# untitled.net
KiCad netlist of a schematic drawn in EAGLE
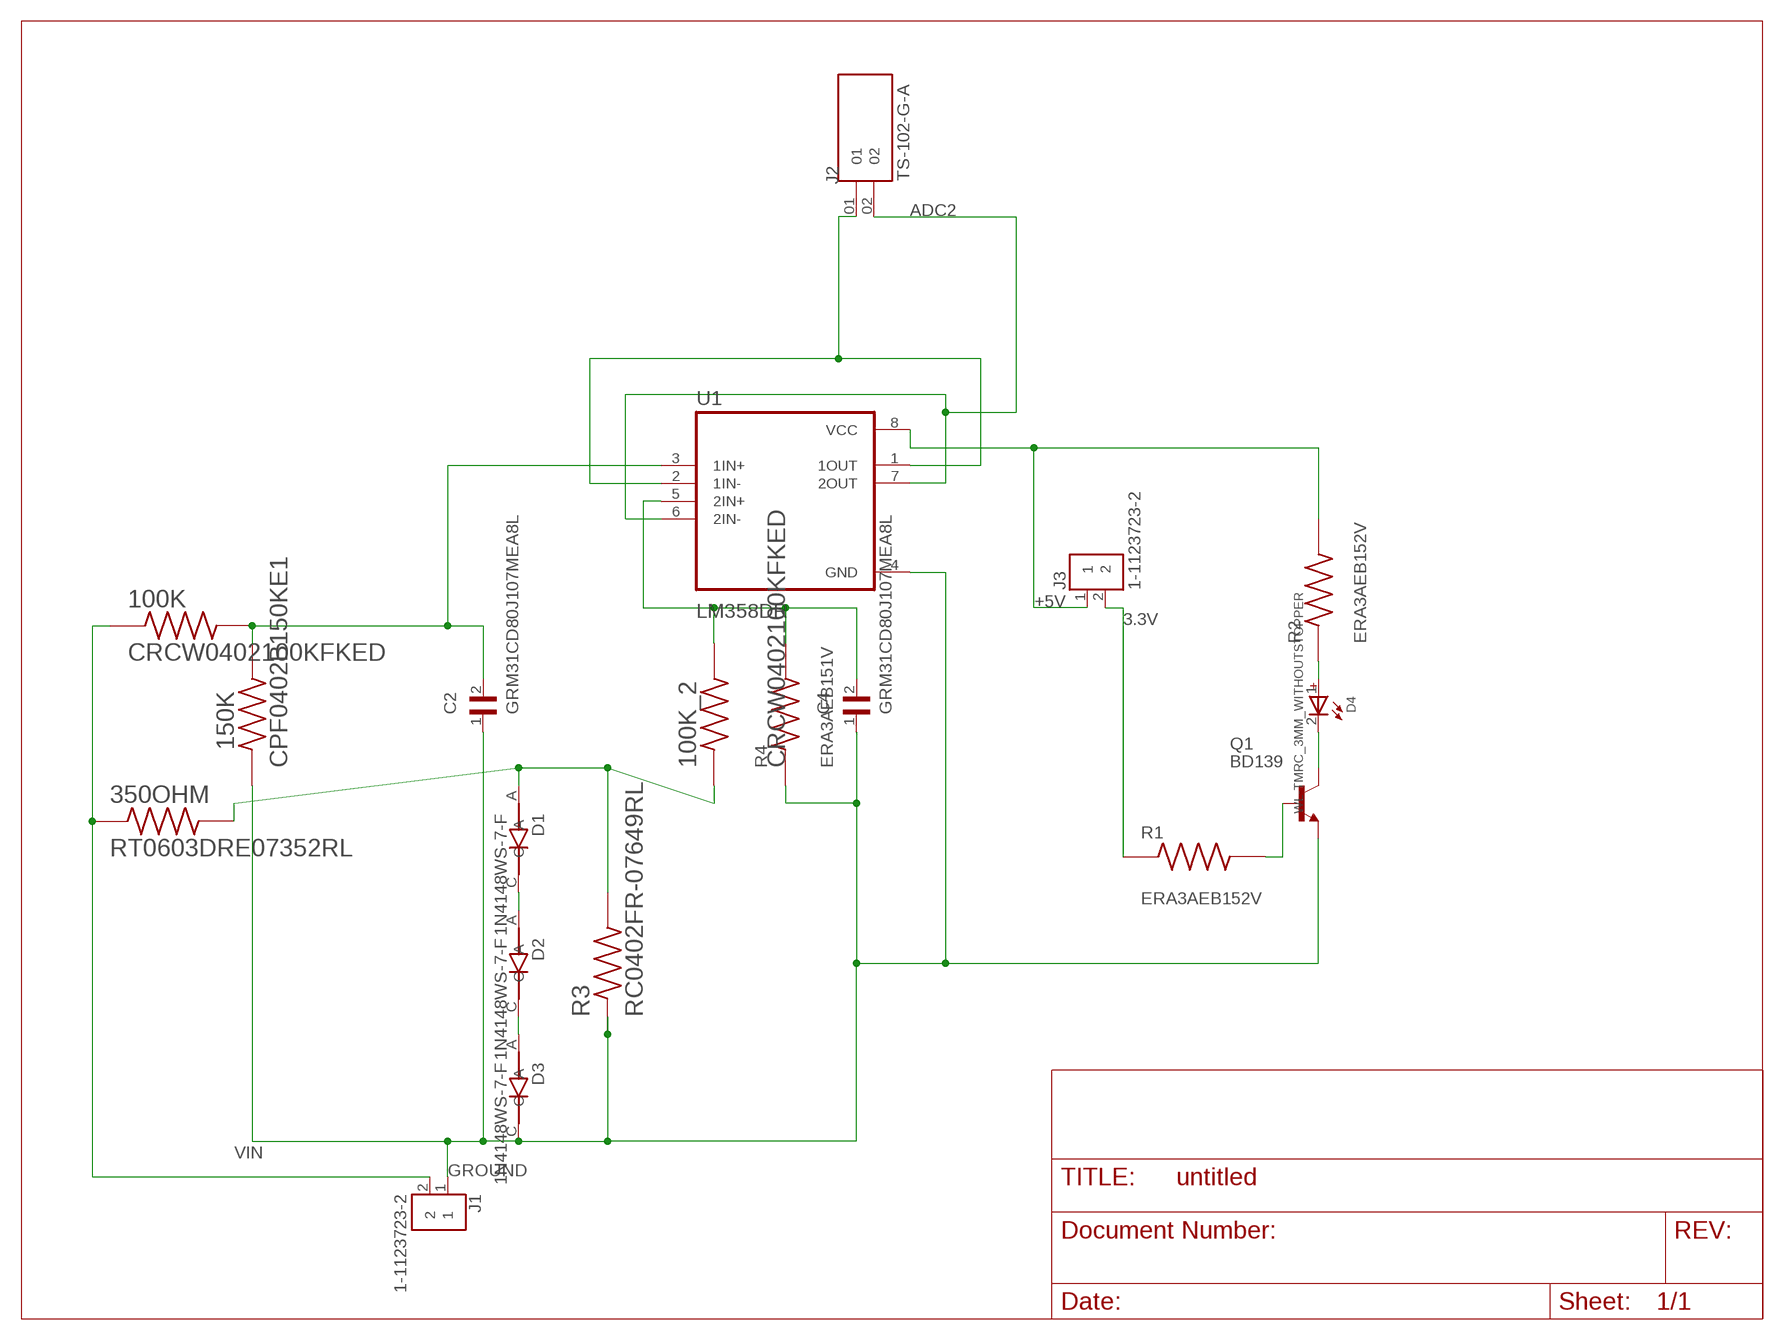
[diagram p0: schematic, sheet 1]

(export (version "E")
  (design (tool "Eeschema 10.0.6"))
  (components
    (comp (ref "100K")
      (value "CRCW0402100KFKED")
      (footprint "eagle-import:RESC1005X40N")
      (libsource (lib "eagle-import") (part "CRCW0402100KFKED"))
    )
    (comp (ref "100K_2")
      (value "CRCW0402100KFKED")
      (footprint "eagle-import:RESC1005X40N")
      (libsource (lib "eagle-import") (part "CRCW0402100KFKED"))
    )
    (comp (ref "150K")
      (value "CPF0402B150KE1")
      (footprint "eagle-import:RESC1005X35N")
      (fields
        (field (name "COMMENT") "3-1879216-2")
        (field (name "MF") "TE Connectivity")
        (field (name "TOLERANCE") ".1%")
      )
      (libsource (lib "eagle-import") (part "CPF0402B150KE1"))
    )
    (comp (ref "350OHM")
      (value "RT0603DRE07352RL")
      (footprint "eagle-import:RESC1608X55N")
      (libsource (lib "eagle-import") (part "RT0603DRE07352RL"))
    )
    (comp (ref "C2")
      (value "GRM31CD80J107MEA8L")
      (footprint "eagle-import:CAPC3216X190N")
      (fields (field (name "DIGIKEY_PART_NUMBER") "490-GRM31CD80J107MEA8LTR-ND") (field (name "MF") "Murata"))
      (libsource (lib "eagle-import") (part "GRM31CD80J107MEA8L"))
    )
    (comp (ref "C4")
      (value "GRM31CD80J107MEA8L")
      (footprint "eagle-import:CAPC3216X190N")
      (fields (field (name "DIGIKEY_PART_NUMBER") "490-GRM31CD80J107MEA8LTR-ND") (field (name "MF") "Murata"))
      (libsource (lib "eagle-import") (part "GRM31CD80J107MEA8L"))
    )
    (comp (ref "D1")
      (value "1N4148WS-7-F")
      (footprint "eagle-import:SOD2513X120N")
      (fields (field (name "MF") "Diodes Inc."))
      (libsource (lib "eagle-import") (part "1N4148WS-7-F"))
    )
    (comp (ref "D2")
      (value "1N4148WS-7-F")
      (footprint "eagle-import:SOD2513X120N")
      (fields (field (name "MF") "Diodes Inc."))
      (libsource (lib "eagle-import") (part "1N4148WS-7-F"))
    )
    (comp (ref "D3")
      (value "1N4148WS-7-F")
      (footprint "eagle-import:SOD2513X120N")
      (fields (field (name "MF") "Diodes Inc."))
      (libsource (lib "eagle-import") (part "1N4148WS-7-F"))
    )
    (comp (ref "D4")
      (value "WL-TMRC_3MM_WITHOUTSTOPPER")
      (footprint "eagle-import:WL-TMRC_3MM")
      (libsource (lib "eagle-import") (part "WL-TMRC_3MM_WITHOUTSTOPPER"))
    )
    (comp (ref "J1")
      (value "1-1123723-2")
      (footprint "eagle-import:TE_1-1123723-2")
      (fields (field (name "MF") "TE Connectivity"))
      (libsource (lib "eagle-import") (part "1-1123723-2"))
    )
    (comp (ref "J2")
      (value "TS-102-G-A")
      (footprint "eagle-import:SAMTEC_TS-102-G-A")
      (fields (field (name "MANUFACTURER") "Samtec Inc."))
      (libsource (lib "eagle-import") (part "TS-102-G-A"))
    )
    (comp (ref "J3")
      (value "1-1123723-2")
      (footprint "eagle-import:TE_1-1123723-2")
      (fields (field (name "MF") "TE Connectivity"))
      (libsource (lib "eagle-import") (part "1-1123723-2"))
    )
    (comp (ref "Q1")
      (value "BD139")
      (footprint "eagle-import:TO126")
      (fields (field (name "MF") "STMicroelectronics"))
      (libsource (lib "eagle-import") (part "BD139"))
    )
    (comp (ref "R1")
      (value "ERA3AEB152V")
      (footprint "eagle-import:RES_ERA3AEB152V")
      (fields (field (name "MANUFACTURER") "Panasonic"))
      (libsource (lib "eagle-import") (part "ERA3AEB152V"))
    )
    (comp (ref "R2")
      (value "ERA3AEB152V")
      (footprint "eagle-import:RES_ERA3AEB152V")
      (fields (field (name "MANUFACTURER") "Panasonic"))
      (libsource (lib "eagle-import") (part "ERA3AEB152V"))
    )
    (comp (ref "R3")
      (value "RC0402FR-07649RL")
      (footprint "eagle-import:RESC1005X40N")
      (libsource (lib "eagle-import") (part "RC0402FR-07649RL"))
    )
    (comp (ref "R4")
      (value "ERA3AEB151V")
      (footprint "eagle-import:RES_ERA3AEB151V")
      (fields (field (name "MANUFACTURER") "Panasonic"))
      (libsource (lib "eagle-import") (part "ERA3AEB151V"))
    )
    (comp (ref "U1")
      (value "LM358DR")
      (footprint "eagle-import:SOIC127P599X175-8N")
      (libsource (lib "eagle-import") (part "LM358DR"))
    )
  )
  (nets
    (net (code "1") (name "/+5V") (class "Default")
      (node (ref "J3") (pin "1") (pinfunction "1_1") (pintype "passive"))
      (node (ref "R2") (pin "2") (pinfunction "2_2") (pintype "passive"))
      (node (ref "U1") (pin "8") (pinfunction "VCC_8") (pintype "power_in"))
    )
    (net (code "2") (name "/3.3V") (class "Default")
      (node (ref "J3") (pin "2") (pinfunction "2_2") (pintype "passive"))
      (node (ref "R1") (pin "1") (pinfunction "1_1") (pintype "passive"))
    )
    (net (code "3") (name "/ADC2") (class "Default")
      (node (ref "J2") (pin "02") (pinfunction "02_02") (pintype "passive"))
      (node (ref "U1") (pin "6") (pinfunction "2IN-_6") (pintype "input"))
      (node (ref "U1") (pin "7") (pinfunction "2OUT_7") (pintype "output"))
    )
    (net (code "4") (name "/GROUND") (class "Default")
      (node (ref "150K") (pin "1") (pinfunction "1_1") (pintype "passive"))
      (node (ref "C2") (pin "1") (pinfunction "1_1") (pintype "passive"))
      (node (ref "C4") (pin "1") (pinfunction "1_1") (pintype "passive"))
      (node (ref "D3") (pin "C") (pinfunction "C_C") (pintype "passive"))
      (node (ref "J1") (pin "1") (pinfunction "1_1") (pintype "passive"))
      (node (ref "Q1") (pin "1") (pinfunction "E_1") (pintype "passive"))
      (node (ref "R3") (pin "1") (pinfunction "1_1") (pintype "passive"))
      (node (ref "R4") (pin "1") (pinfunction "1_1") (pintype "passive"))
      (node (ref "U1") (pin "4") (pinfunction "GND_4") (pintype "power_in"))
    )
    (net (code "5") (name "/VIN") (class "Default")
      (node (ref "100K") (pin "1") (pinfunction "1_1") (pintype "passive"))
      (node (ref "350OHM") (pin "1") (pinfunction "1_1") (pintype "passive"))
      (node (ref "J1") (pin "2") (pinfunction "2_2") (pintype "passive"))
    )
    (net (code "6") (name "Net-(100K_2-Pad1)") (class "Default")
      (node (ref "100K_2") (pin "1") (pinfunction "1_1") (pintype "passive"))
      (node (ref "350OHM") (pin "2") (pinfunction "2_2") (pintype "passive"))
      (node (ref "D1") (pin "A") (pinfunction "A_A") (pintype "passive"))
      (node (ref "R3") (pin "2") (pinfunction "2_2") (pintype "passive"))
    )
    (net (code "7") (name "Net-(D1-PadC)") (class "Default")
      (node (ref "D1") (pin "C") (pinfunction "C_C") (pintype "passive"))
      (node (ref "D2") (pin "A") (pinfunction "A_A") (pintype "passive"))
    )
    (net (code "8") (name "Net-(D2-PadC)") (class "Default")
      (node (ref "D2") (pin "C") (pinfunction "C_C") (pintype "passive"))
      (node (ref "D3") (pin "A") (pinfunction "A_A") (pintype "passive"))
    )
    (net (code "9") (name "Net-(D4-+)") (class "Default")
      (node (ref "D4") (pin "1") (pinfunction "+_1") (pintype "passive"))
      (node (ref "R2") (pin "1") (pinfunction "1_1") (pintype "passive"))
    )
    (net (code "10") (name "Net-(D4--)") (class "Default")
      (node (ref "D4") (pin "2") (pinfunction "-_2") (pintype "passive"))
      (node (ref "Q1") (pin "2") (pinfunction "C_2") (pintype "passive"))
    )
    (net (code "11") (name "Net-(Q1-B)") (class "Default")
      (node (ref "Q1") (pin "3") (pinfunction "B_3") (pintype "passive"))
      (node (ref "R1") (pin "2") (pinfunction "2_2") (pintype "passive"))
    )
    (net (code "12") (name "Net-(U1-1IN+)") (class "Default")
      (node (ref "100K") (pin "2") (pinfunction "2_2") (pintype "passive"))
      (node (ref "150K") (pin "2") (pinfunction "2_2") (pintype "passive"))
      (node (ref "C2") (pin "2") (pinfunction "2_2") (pintype "passive"))
      (node (ref "U1") (pin "3") (pinfunction "1IN+_3") (pintype "input"))
    )
    (net (code "13") (name "Net-(U1-1IN-)") (class "Default")
      (node (ref "J2") (pin "01") (pinfunction "01_01") (pintype "passive"))
      (node (ref "U1") (pin "1") (pinfunction "1OUT_1") (pintype "output"))
      (node (ref "U1") (pin "2") (pinfunction "1IN-_2") (pintype "input"))
    )
    (net (code "14") (name "Net-(U1-2IN+)") (class "Default")
      (node (ref "100K_2") (pin "2") (pinfunction "2_2") (pintype "passive"))
      (node (ref "C4") (pin "2") (pinfunction "2_2") (pintype "passive"))
      (node (ref "R4") (pin "2") (pinfunction "2_2") (pintype "passive"))
      (node (ref "U1") (pin "5") (pinfunction "2IN+_5") (pintype "input"))
    )
  )
)
